# breadboard_isp.net
KiCad netlist of a schematic drawn in EAGLE
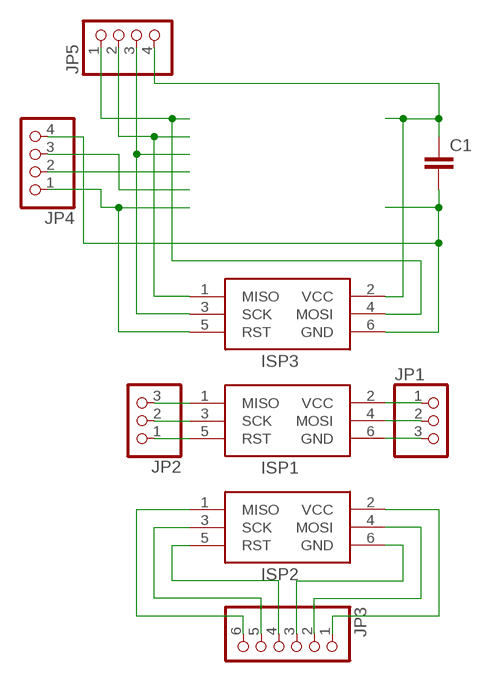
[diagram p0: schematic, sheet 1]

(export (version "E")
  (design (tool "Eeschema 10.0.6"))
  (components
    (comp (ref "C1")
      (value "C-EU025-025X050")
      (footprint "eagle-import:C025-025X050")
      (libsource (lib "eagle-import") (part "C-EU025-025X050"))
    )
    (comp (ref "ISP1")
      (value "AVRISP-6")
      (footprint "eagle-import:AVRISP")
      (libsource (lib "eagle-import") (part "AVRISP-6"))
    )
    (comp (ref "ISP2")
      (value "AVRISP-6")
      (footprint "eagle-import:AVRISP")
      (libsource (lib "eagle-import") (part "AVRISP-6"))
    )
    (comp (ref "ISP3")
      (value "AVRISP-6")
      (footprint "eagle-import:AVRISP")
      (libsource (lib "eagle-import") (part "AVRISP-6"))
    )
    (comp (ref "JP1")
      (value "PINHD-1X3")
      (footprint "eagle-import:1X03")
      (libsource (lib "eagle-import") (part "PINHD-1X3"))
    )
    (comp (ref "JP2")
      (value "PINHD-1X3")
      (footprint "eagle-import:1X03")
      (libsource (lib "eagle-import") (part "PINHD-1X3"))
    )
    (comp (ref "JP3")
      (value "PINHD-1X6")
      (footprint "eagle-import:1X06")
      (libsource (lib "eagle-import") (part "PINHD-1X6"))
    )
    (comp (ref "JP4")
      (value "PINHD-1X4")
      (footprint "eagle-import:1X04")
      (libsource (lib "eagle-import") (part "PINHD-1X4"))
    )
    (comp (ref "JP5")
      (value "PINHD-1X4")
      (footprint "eagle-import:1X04")
      (libsource (lib "eagle-import") (part "PINHD-1X4"))
    )
  )
  (nets
    (net (code "1") (name "Net-(ISP1-GND)") (class "Default")
      (node (ref "ISP1") (pin "6") (pinfunction "GND_6") (pintype "power_in"))
      (node (ref "JP1") (pin "3") (pinfunction "3_3") (pintype "passive"))
    )
    (net (code "2") (name "Net-(ISP1-MISO)") (class "Default")
      (node (ref "ISP1") (pin "1") (pinfunction "MISO_1") (pintype "input"))
      (node (ref "JP2") (pin "3") (pinfunction "3_3") (pintype "passive"))
    )
    (net (code "3") (name "Net-(ISP1-MOSI)") (class "Default")
      (node (ref "ISP1") (pin "4") (pinfunction "MOSI_4") (pintype "output"))
      (node (ref "JP1") (pin "2") (pinfunction "2_2") (pintype "passive"))
    )
    (net (code "4") (name "Net-(ISP1-RST)") (class "Default")
      (node (ref "ISP1") (pin "5") (pinfunction "RST_5") (pintype "output"))
      (node (ref "JP2") (pin "1") (pinfunction "1_1") (pintype "passive"))
    )
    (net (code "5") (name "Net-(ISP1-SCK)") (class "Default")
      (node (ref "ISP1") (pin "3") (pinfunction "SCK_3") (pintype "output"))
      (node (ref "JP2") (pin "2") (pinfunction "2_2") (pintype "passive"))
    )
    (net (code "6") (name "Net-(ISP1-VCC)") (class "Default")
      (node (ref "ISP1") (pin "2") (pinfunction "VCC_2") (pintype "power_in"))
      (node (ref "JP1") (pin "1") (pinfunction "1_1") (pintype "passive"))
    )
    (net (code "7") (name "Net-(ISP2-GND)") (class "Default")
      (node (ref "ISP2") (pin "6") (pinfunction "GND_6") (pintype "power_in"))
      (node (ref "JP3") (pin "3") (pinfunction "3_3") (pintype "passive"))
    )
    (net (code "8") (name "Net-(ISP2-MISO)") (class "Default")
      (node (ref "ISP2") (pin "1") (pinfunction "MISO_1") (pintype "input"))
      (node (ref "JP3") (pin "6") (pinfunction "6_6") (pintype "passive"))
    )
    (net (code "9") (name "Net-(ISP2-MOSI)") (class "Default")
      (node (ref "ISP2") (pin "4") (pinfunction "MOSI_4") (pintype "output"))
      (node (ref "JP3") (pin "2") (pinfunction "2_2") (pintype "passive"))
    )
    (net (code "10") (name "Net-(ISP2-RST)") (class "Default")
      (node (ref "ISP2") (pin "5") (pinfunction "RST_5") (pintype "output"))
      (node (ref "JP3") (pin "4") (pinfunction "4_4") (pintype "passive"))
    )
    (net (code "11") (name "Net-(ISP2-SCK)") (class "Default")
      (node (ref "ISP2") (pin "3") (pinfunction "SCK_3") (pintype "output"))
      (node (ref "JP3") (pin "5") (pinfunction "5_5") (pintype "passive"))
    )
    (net (code "12") (name "Net-(ISP2-VCC)") (class "Default")
      (node (ref "ISP2") (pin "2") (pinfunction "VCC_2") (pintype "power_in"))
      (node (ref "JP3") (pin "1") (pinfunction "1_1") (pintype "passive"))
    )
    (net (code "13") (name "Net-(ISP3-GND)") (class "Default")
      (node (ref "C1") (pin "2") (pinfunction "2_2") (pintype "passive"))
      (node (ref "ISP3") (pin "6") (pinfunction "GND_6") (pintype "power_in"))
      (node (ref "JP4") (pin "4") (pinfunction "4_4") (pintype "passive"))
    )
    (net (code "14") (name "Net-(ISP3-MISO)") (class "Default")
      (node (ref "ISP3") (pin "1") (pinfunction "MISO_1") (pintype "input"))
      (node (ref "JP5") (pin "2") (pinfunction "2_2") (pintype "passive"))
    )
    (net (code "15") (name "Net-(ISP3-MOSI)") (class "Default")
      (node (ref "ISP3") (pin "4") (pinfunction "MOSI_4") (pintype "output"))
      (node (ref "JP5") (pin "1") (pinfunction "1_1") (pintype "passive"))
    )
    (net (code "16") (name "Net-(ISP3-RST)") (class "Default")
      (node (ref "ISP3") (pin "5") (pinfunction "RST_5") (pintype "output"))
      (node (ref "JP4") (pin "1") (pinfunction "1_1") (pintype "passive"))
    )
    (net (code "17") (name "Net-(ISP3-SCK)") (class "Default")
      (node (ref "ISP3") (pin "3") (pinfunction "SCK_3") (pintype "output"))
      (node (ref "JP5") (pin "3") (pinfunction "3_3") (pintype "passive"))
    )
    (net (code "18") (name "Net-(ISP3-VCC)") (class "Default")
      (node (ref "C1") (pin "1") (pinfunction "1_1") (pintype "passive"))
      (node (ref "ISP3") (pin "2") (pinfunction "VCC_2") (pintype "power_in"))
      (node (ref "JP5") (pin "4") (pinfunction "4_4") (pintype "passive"))
    )
    (net (code "19") (name "unconnected-(JP4-Pad2)") (class "Default")
      (node (ref "JP4") (pin "2") (pinfunction "2_2") (pintype "passive"))
    )
    (net (code "20") (name "unconnected-(JP4-Pad3)") (class "Default")
      (node (ref "JP4") (pin "3") (pinfunction "3_3") (pintype "passive"))
    )
  )
)
